# MCU_Signals.net
KiCad netlist of a schematic drawn in Altium Designer
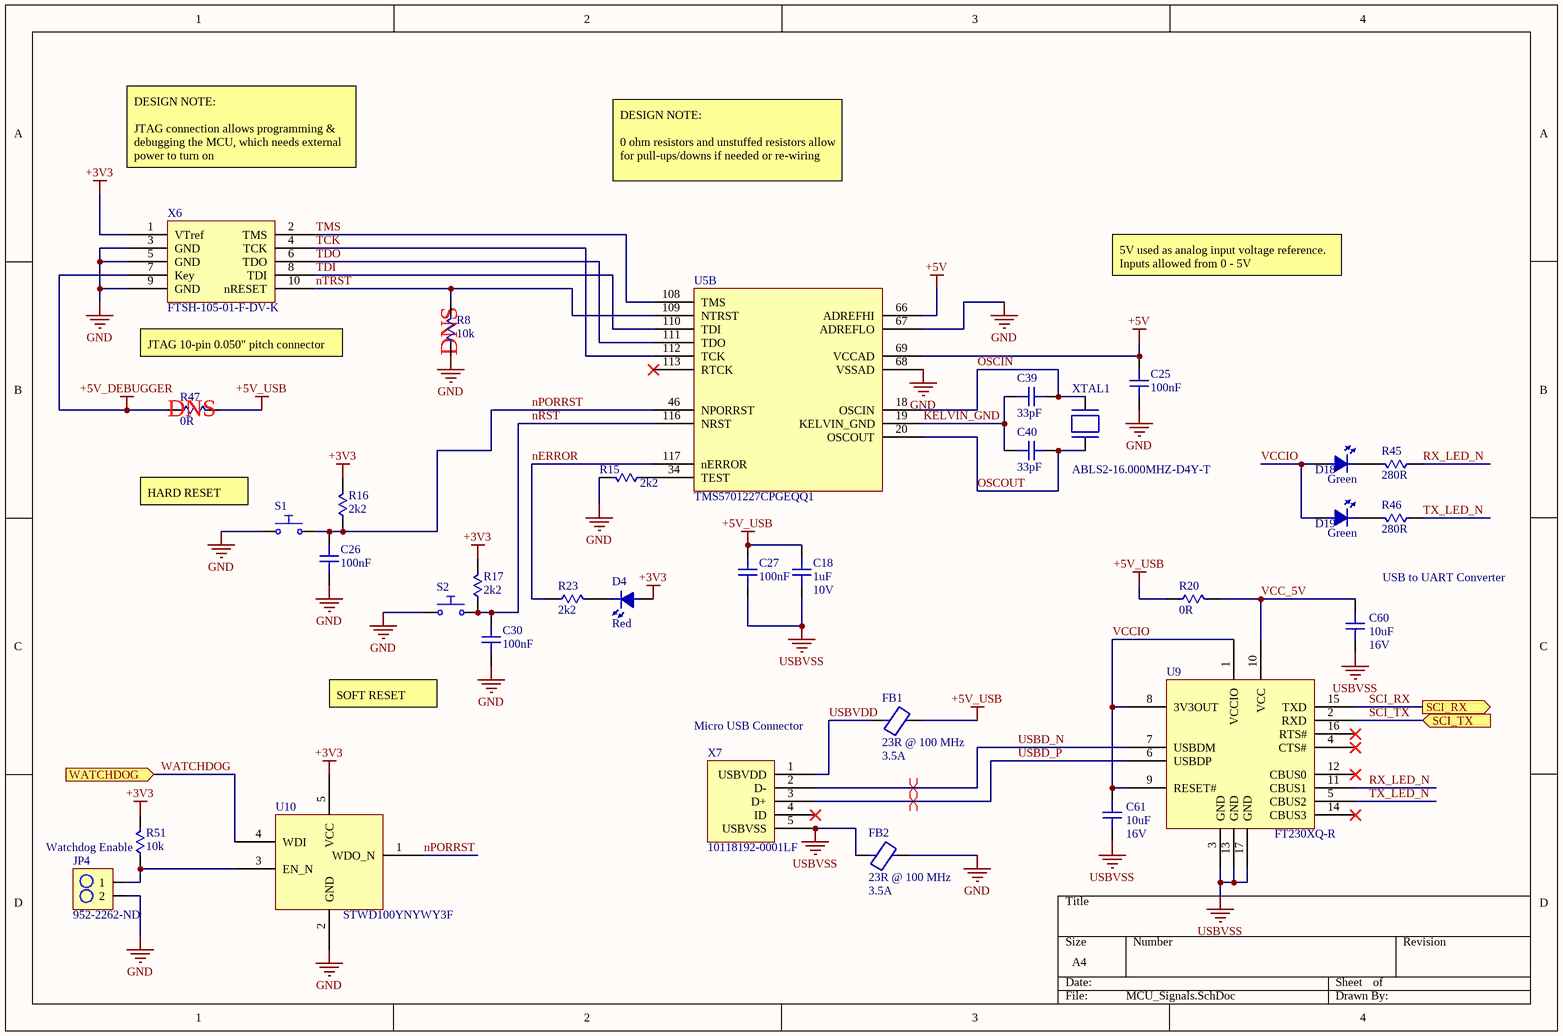
[diagram p0: MCU_Signals.SchDoc]

(export (version "E")
  (design (tool "Eeschema 10.0.6"))
  (components
    (comp (ref "C18")
      (value "1uF")
      (footprint "C0402")
      (description "CAP MLCC 1uF 10V 0402 X5R 20% SMD 0402 85C Paper T/R")
      (fields
        (field (name "MANUFACTURER") "Samsung")
        (field (name "MANUFACTURER PART NUMBER") "CL05A105MP5NNNC")
        (field (name "VOLTAGE RATING") "10V")
      )
      (libsource (lib "PHANTOM_LIBRARY") (part "CL05A105MP5NNNC"))
    )
    (comp (ref "C25")
      (value "100nF")
      (footprint "C0402")
      (description "CAP MLCC 0.1uF 10V X5R 0402 20% SMD 0402 85C Paper T/R")
      (fields
        (field (name "MANUFACTURER") "Samsung")
        (field (name "MANUFACTURER PART NUMBER") "CL05A104MP5NNNC")
      )
      (libsource (lib "PHANTOM_LIBRARY") (part "CL05A104MP5NNNC"))
    )
    (comp (ref "C26")
      (value "100nF")
      (footprint "C0402")
      (description "CAP MLCC 0.1uF 10V X5R 0402 20% SMD 0402 85C Paper T/R")
      (fields
        (field (name "MANUFACTURER") "Samsung")
        (field (name "MANUFACTURER PART NUMBER") "CL05A104MP5NNNC")
      )
      (libsource (lib "PHANTOM_LIBRARY") (part "CL05A104MP5NNNC"))
    )
    (comp (ref "C27")
      (value "100nF")
      (footprint "C0402")
      (description "CAP MLCC 0.1uF 10V X5R 0402 20% SMD 0402 85C Paper T/R")
      (fields
        (field (name "MANUFACTURER") "Samsung")
        (field (name "MANUFACTURER PART NUMBER") "CL05A104MP5NNNC")
      )
      (libsource (lib "PHANTOM_LIBRARY") (part "CL05A104MP5NNNC"))
    )
    (comp (ref "C30")
      (value "100nF")
      (footprint "C0402")
      (description "CAP MLCC 0.1uF 10V X5R 0402 20% SMD 0402 85C Paper T/R")
      (fields
        (field (name "MANUFACTURER") "Samsung")
        (field (name "MANUFACTURER PART NUMBER") "CL05A104MP5NNNC")
      )
      (libsource (lib "PHANTOM_LIBRARY") (part "CL05A104MP5NNNC"))
    )
    (comp (ref "C39")
      (value "33pF")
      (footprint "C0402")
      (description "CAP MLCC 33pF 10V C0G, NP0 0402 (1005 Metric) 0.039\" L x 0.020\" W (1.00mm x 0.50mm)")
      (fields
        (field (name "MANUFACTURER") "Wurth Electronics")
        (field (name "MANUFACTURER PART NUMBER") "885012005010")
      )
      (libsource (lib "PHANTOM_LIBRARY") (part "885012005010"))
    )
    (comp (ref "C40")
      (value "33pF")
      (footprint "C0402")
      (description "CAP MLCC 33pF 10V C0G, NP0 0402 (1005 Metric) 0.039\" L x 0.020\" W (1.00mm x 0.50mm)")
      (fields
        (field (name "MANUFACTURER") "Wurth Electronics")
        (field (name "MANUFACTURER PART NUMBER") "885012005010")
      )
      (libsource (lib "PHANTOM_LIBRARY") (part "885012005010"))
    )
    (comp (ref "C60")
      (value "10uF")
      (footprint "C0805")
      (description "CAP CER 10uF 16V X5R 10% SMD 0805 85C T/R")
      (fields
        (field (name "MANUFACTURER") "Samsung")
        (field (name "MANUFACTURER PART NUMBER") "CL21A106KOQNNNE")
        (field (name "VOLTAGE RATING") "16V")
      )
      (libsource (lib "ESC_SYMBOLS") (part "CL21A106KOQNNNE"))
    )
    (comp (ref "C61")
      (value "10uF")
      (footprint "C0805")
      (description "CAP CER 10uF 16V X5R 10% SMD 0805 85C T/R")
      (fields
        (field (name "MANUFACTURER") "Samsung")
        (field (name "MANUFACTURER PART NUMBER") "CL21A106KOQNNNE")
        (field (name "VOLTAGE RATING") "16V")
      )
      (libsource (lib "ESC_SYMBOLS") (part "CL21A106KOQNNNE"))
    )
    (comp (ref "D4")
      (value "Red")
      (footprint "LED_0603")
      (description "LED RED CLEAR 0603 SMD 625 nm, 2 V, 30 mA, 250 mcd")
      (fields
        (field (name "MANUFACTURER") "Wurth Electronics")
        (field (name "MANUFACTURER PART NUMBER") "150060RS75000")
      )
      (libsource (lib "PHANTOM_LIBRARY") (part "150060RS75000"))
    )
    (comp (ref "D18")
      (value "Green")
      (footprint "LED_0603")
      (description "LED GREEN CLEAR 0603 SMD  LED, 0603, B GREEN,  40MCD, 570NM")
      (fields
        (field (name "MANUFACTURER") "Wurth Electronics")
        (field (name "MANUFACTURER PART NUMBER") "150060VS75000")
      )
      (libsource (lib "PHANTOM_LIBRARY") (part "150060VS75000"))
    )
    (comp (ref "D19")
      (value "Green")
      (footprint "LED_0603")
      (description "LED GREEN CLEAR 0603 SMD  LED, 0603, B GREEN,  40MCD, 570NM")
      (fields
        (field (name "MANUFACTURER") "Wurth Electronics")
        (field (name "MANUFACTURER PART NUMBER") "150060VS75000")
      )
      (libsource (lib "PHANTOM_LIBRARY") (part "150060VS75000"))
    )
    (comp (ref "FB1")
      (value "23R @ 100 MHz")
      (footprint "FB_1806")
      (description "FERRITE BEAD Ind Chip Bead Multi-Layer 23Ohm 30% 100MHz Ferrite 3.5A 1806 T/R")
      (fields
        (field (name "MANUFACTURER") "Taiyo Yuden")
        (field (name "MANUFACTURER PART NUMBER") "FBMJ4516HL230NTV")
        (field (name "MAX CURRENT RATING") "3.5A")
      )
      (libsource (lib "PHANTOM_LIBRARY") (part "FBMJ4516HL230NTV"))
    )
    (comp (ref "FB2")
      (value "23R @ 100 MHz")
      (footprint "FB_1806")
      (description "FERRITE BEAD Ind Chip Bead Multi-Layer 23Ohm 30% 100MHz Ferrite 3.5A 1806 T/R")
      (fields
        (field (name "MANUFACTURER") "Taiyo Yuden")
        (field (name "MANUFACTURER PART NUMBER") "FBMJ4516HL230NTV")
        (field (name "MAX CURRENT RATING") "3.5A")
      )
      (libsource (lib "PHANTOM_LIBRARY") (part "FBMJ4516HL230NTV"))
    )
    (comp (ref "JP4")
      (value "952-2262-ND")
      (footprint "2PIN_HEADER")
      (description "CONN_HeaderPins2pos Headers & Wire Housings 02 SIL VERTICAL PIN HEADER TIN")
      (fields (field (name "MANUFACTURER") "Harwin") (field (name "MANUFACTURER PART NUMBER") "M20-9990246"))
      (libsource (lib "PHANTOM_LIBRARY") (part "M20-9990246"))
    )
    (comp (ref "R8")
      (value "10k")
      (footprint "R0402")
      (description "RES SMD 10K OHM 5% 1/16W 0402")
      (fields
        (field (name "MANUFACTURER") "Yageo")
        (field (name "MANUFACTURER PART NUMBER") "RC0402JR-0710KL")
      )
      (libsource (lib "PHANTOM_LIBRARY") (part "RC0402JR-0710KL"))
    )
    (comp (ref "R15")
      (value "2k2")
      (footprint "R0402")
      (description "RES SMD 2.2K OHM 5% 1/16W 0402")
      (fields
        (field (name "MANUFACTURER") "Yageo")
        (field (name "MANUFACTURER PART NUMBER") "RC0402JR-072K2L")
      )
      (libsource (lib "PHANTOM_LIBRARY") (part "RC0402JR-072K2L"))
    )
    (comp (ref "R16")
      (value "2k2")
      (footprint "R0402")
      (description "RES SMD 2.2K OHM 5% 1/16W 0402")
      (fields
        (field (name "MANUFACTURER") "Yageo")
        (field (name "MANUFACTURER PART NUMBER") "RC0402JR-072K2L")
      )
      (libsource (lib "PHANTOM_LIBRARY") (part "RC0402JR-072K2L"))
    )
    (comp (ref "R17")
      (value "2k2")
      (footprint "R0402")
      (description "RES SMD 2.2K OHM 5% 1/16W 0402")
      (fields
        (field (name "MANUFACTURER") "Yageo")
        (field (name "MANUFACTURER PART NUMBER") "RC0402JR-072K2L")
      )
      (libsource (lib "PHANTOM_LIBRARY") (part "RC0402JR-072K2L"))
    )
    (comp (ref "R20")
      (value "0R")
      (footprint "R0402")
      (description "RES SMD 0 OHM 1/16W 0402")
      (fields
        (field (name "MANUFACTURER") "Yageo")
        (field (name "MANUFACTURER PART NUMBER") "RC0402JR-070RL")
      )
      (libsource (lib "BT_SYMBOLS") (part "RC0402JR-070RL"))
    )
    (comp (ref "R23")
      (value "2k2")
      (footprint "R0402")
      (description "RES SMD 2.2K OHM 5% 1/16W 0402")
      (fields
        (field (name "MANUFACTURER") "Yageo")
        (field (name "MANUFACTURER PART NUMBER") "RC0402JR-072K2L")
      )
      (libsource (lib "PHANTOM_LIBRARY") (part "RC0402JR-072K2L"))
    )
    (comp (ref "R45")
      (value "280R")
      (footprint "R0402")
      (description "RES SMD 280 OHM 1% 1/16W 0402")
      (fields
        (field (name "MANUFACTURER") "Yageo")
        (field (name "MANUFACTURER PART NUMBER") "RC0402FR-07280RL")
      )
      (libsource (lib "PHANTOM_LIBRARY") (part "RC0402FR-07280RL"))
    )
    (comp (ref "R46")
      (value "280R")
      (footprint "R0402")
      (description "RES SMD 280 OHM 1% 1/16W 0402")
      (fields
        (field (name "MANUFACTURER") "Yageo")
        (field (name "MANUFACTURER PART NUMBER") "RC0402FR-07280RL")
      )
      (libsource (lib "PHANTOM_LIBRARY") (part "RC0402FR-07280RL"))
    )
    (comp (ref "R47")
      (value "0R")
      (footprint "R0402")
      (description "RES SMD 0 OHM 1/16W 0402")
      (fields
        (field (name "MANUFACTURER") "Yageo")
        (field (name "MANUFACTURER PART NUMBER") "RC0402JR-070RL")
      )
      (libsource (lib "BT_SYMBOLS") (part "RC0402JR-070RL"))
    )
    (comp (ref "R51")
      (value "10k")
      (footprint "R0402")
      (description "RES SMD 10K OHM 5% 1/16W 0402")
      (fields
        (field (name "MANUFACTURER") "Yageo")
        (field (name "MANUFACTURER PART NUMBER") "RC0402JR-0710KL")
      )
      (libsource (lib "PHANTOM_LIBRARY") (part "RC0402JR-0710KL"))
    )
    (comp (ref "S1")
      (value "PTS645SM43SMTR92LFS")
      (footprint "PUSH_BUTTON")
      (description "SWITCH TACTILE SPST-NO 0.05A 12V")
      (fields (field (name "MANUFACTURER") "ITT C&K"))
      (libsource (lib "PHANTOM_LIBRARY") (part "PTS645SM43SMTR92LFS"))
    )
    (comp (ref "S2")
      (value "PTS645SM43SMTR92LFS")
      (footprint "PUSH_BUTTON")
      (description "SWITCH TACTILE SPST-NO 0.05A 12V")
      (fields (field (name "MANUFACTURER") "ITT C&K"))
      (libsource (lib "PHANTOM_LIBRARY") (part "PTS645SM43SMTR92LFS"))
    )
    (comp (ref "U5")
      (value "TMS5701227CPGEQQ1")
      (footprint "LQFP-144")
      (description "IC MCU 16-Bit/32-Bit Hercules TMS570 ARM Cortex R4F RISC 1280KB Flash 1.2V/3.3V 144-Pin LQFP")
      (fields (field (name "MANUFACTURER") "Texas Instruments"))
      (libsource (lib "PHANTOM_LIBRARY") (part "TMS5701227CPGEQQ1"))
    )
    (comp (ref "U9")
      (value "FT230XQ-R")
      (footprint "QFN16-EP")
      (description "IC USB SERIAL BASIC UART 16QFN")
      (fields (field (name "MANUFACTURER") "FTDI"))
      (libsource (lib "PHANTOM_LIBRARY") (part "FT230XQ-R"))
    )
    (comp (ref "U10")
      (value "STWD100YNYWY3F")
      (footprint "SOT23-5-WATCHDOG")
      (description "IC WATCHDOG TIME CIRCUIT SOT23-5")
      (fields (field (name "MANUFACTURER") "STMicroelectronics"))
      (libsource (lib "PHANTOM_LIBRARY") (part "STWD100YNYWY3F"))
    )
    (comp (ref "X6")
      (value "FTSH-105-01-F-DV-K")
      (footprint "JTAG_50mil_10pin")
      (description "CONN_JTAG_10pin .050 Connector Dual Header 10 Position Surface Mount")
      (fields (field (name "MANUFACTURER") "Samtec"))
      (libsource (lib "PHANTOM_LIBRARY") (part "FTSH-105-01-F-DV-K"))
    )
    (comp (ref "X7")
      (value "10118192-0001LF")
      (footprint "USB_MICRO")
      (description "CONN_USB - micro B USB 2.0 Receptacle Connector 5 Position Surface Mount, Right Angle, Horizontal")
      (fields (field (name "MANUFACTURER") "Amphenol FCI"))
      (libsource (lib "PHANTOM_LIBRARY") (part "10118192-0001LF"))
    )
    (comp (ref "XTAL1")
      (value "ABLS2-16.000MHZ-D4Y-T")
      (footprint "XTAL")
      (description "XTAL 16MHz ±30ppm Crystal 18pF 40 Ohm -40°C ~ 85°C  Surface Mount HC49/US")
      (fields (field (name "MANUFACTURER") "Abracon") (field (name "TOLERANCE") "30ppm"))
      (libsource (lib "PHANTOM_LIBRARY") (part "ABLS2-16.000MHZ-D4Y-T"))
    )
  )
  (nets
    (net (code "1") (name "+3V3") (class "Default")
      (node (ref "D4") (pin "1") (pinfunction "1_1") (pintype "passive"))
      (node (ref "R16") (pin "2") (pinfunction "2_2") (pintype "passive"))
      (node (ref "R17") (pin "2") (pinfunction "2_2") (pintype "passive"))
      (node (ref "R51") (pin "2") (pinfunction "2_2") (pintype "passive"))
      (node (ref "U10") (pin "5") (pinfunction "VCC_5") (pintype "passive"))
      (node (ref "X6") (pin "1") (pinfunction "VTref_1") (pintype "passive"))
    )
    (net (code "2") (name "+5V") (class "Default")
      (node (ref "C25") (pin "2") (pinfunction "2_2") (pintype "passive"))
      (node (ref "U5") (pin "66") (pinfunction "ADREFHI_66") (pintype "passive"))
      (node (ref "U5") (pin "69") (pinfunction "VCCAD_69") (pintype "passive"))
    )
    (net (code "3") (name "+5V_DEBUGGER") (class "Default")
      (node (ref "R47") (pin "1") (pinfunction "1_1") (pintype "passive"))
      (node (ref "X6") (pin "7") (pinfunction "Key_7") (pintype "passive"))
    )
    (net (code "4") (name "+5V_USB") (class "Default")
      (node (ref "C18") (pin "2") (pinfunction "2_2") (pintype "passive"))
      (node (ref "C27") (pin "1") (pinfunction "1_1") (pintype "passive"))
      (node (ref "FB1") (pin "2") (pinfunction "2_2") (pintype "passive"))
      (node (ref "R20") (pin "1") (pinfunction "1_1") (pintype "passive"))
      (node (ref "R47") (pin "2") (pinfunction "2_2") (pintype "passive"))
    )
    (net (code "5") (name "/KELVIN_GND") (class "Default")
      (node (ref "C39") (pin "2") (pinfunction "2_2") (pintype "passive"))
      (node (ref "C40") (pin "2") (pinfunction "2_2") (pintype "passive"))
      (node (ref "U5") (pin "19") (pinfunction "KELVIN_GND_19") (pintype "passive"))
    )
    (net (code "6") (name "/OSCIN") (class "Default")
      (node (ref "C39") (pin "1") (pinfunction "1_1") (pintype "passive"))
      (node (ref "U5") (pin "18") (pinfunction "OSCIN_18") (pintype "passive"))
      (node (ref "XTAL1") (pin "1") (pintype "passive"))
    )
    (net (code "7") (name "/OSCOUT") (class "Default")
      (node (ref "C40") (pin "1") (pinfunction "1_1") (pintype "passive"))
      (node (ref "U5") (pin "20") (pinfunction "OSCOUT_20") (pintype "passive"))
      (node (ref "XTAL1") (pin "2") (pintype "passive"))
    )
    (net (code "8") (name "/RX_LED_N") (class "Default")
      (node (ref "R45") (pin "1") (pinfunction "1_1") (pintype "passive"))
      (node (ref "U9") (pin "11") (pinfunction "CBUS1_11") (pintype "passive"))
    )
    (net (code "9") (name "/SCI_RX") (class "Default")
      (node (ref "U9") (pin "15") (pinfunction "TXD_15") (pintype "passive"))
    )
    (net (code "10") (name "/SCI_TX") (class "Default")
      (node (ref "U9") (pin "2") (pinfunction "RXD_2") (pintype "passive"))
    )
    (net (code "11") (name "/TCK") (class "Default")
      (node (ref "U5") (pin "112") (pinfunction "TCK_112") (pintype "passive"))
      (node (ref "X6") (pin "4") (pinfunction "TCK_4") (pintype "passive"))
    )
    (net (code "12") (name "/TDI") (class "Default")
      (node (ref "U5") (pin "110") (pinfunction "TDI_110") (pintype "passive"))
      (node (ref "X6") (pin "8") (pinfunction "TDI_8") (pintype "passive"))
    )
    (net (code "13") (name "/TDO") (class "Default")
      (node (ref "U5") (pin "111") (pinfunction "TDO_111") (pintype "passive"))
      (node (ref "X6") (pin "6") (pinfunction "TDO_6") (pintype "passive"))
    )
    (net (code "14") (name "/TMS") (class "Default")
      (node (ref "U5") (pin "108") (pinfunction "TMS_108") (pintype "passive"))
      (node (ref "X6") (pin "2") (pinfunction "TMS_2") (pintype "passive"))
    )
    (net (code "15") (name "/TX_LED_N") (class "Default")
      (node (ref "R46") (pin "1") (pinfunction "1_1") (pintype "passive"))
      (node (ref "U9") (pin "5") (pinfunction "CBUS2_5") (pintype "passive"))
    )
    (net (code "16") (name "/USBD_N") (class "Default")
      (node (ref "U9") (pin "7") (pinfunction "USBDM_7") (pintype "passive"))
      (node (ref "X7") (pin "2") (pinfunction "D-_2") (pintype "passive"))
    )
    (net (code "17") (name "/USBD_P") (class "Default")
      (node (ref "U9") (pin "6") (pinfunction "USBDP_6") (pintype "passive"))
      (node (ref "X7") (pin "3") (pinfunction "D+_3") (pintype "passive"))
    )
    (net (code "18") (name "/USBVDD") (class "Default")
      (node (ref "FB1") (pin "1") (pinfunction "1_1") (pintype "passive"))
      (node (ref "X7") (pin "1") (pinfunction "USBVDD_1") (pintype "passive"))
    )
    (net (code "19") (name "/VCCIO") (class "Default")
      (node (ref "C61") (pin "2") (pinfunction "2_2") (pintype "passive"))
      (node (ref "D18") (pin "1") (pinfunction "1_1") (pintype "passive"))
      (node (ref "D19") (pin "1") (pinfunction "1_1") (pintype "passive"))
      (node (ref "U9") (pin "1") (pinfunction "VCCIO_1") (pintype "passive"))
      (node (ref "U9") (pin "8") (pinfunction "3V3OUT_8") (pintype "passive"))
      (node (ref "U9") (pin "9") (pinfunction "RESET#_9") (pintype "passive"))
    )
    (net (code "20") (name "/VCC_5V") (class "Default")
      (node (ref "C60") (pin "2") (pinfunction "2_2") (pintype "passive"))
      (node (ref "R20") (pin "2") (pinfunction "2_2") (pintype "passive"))
      (node (ref "U9") (pin "10") (pinfunction "VCC_10") (pintype "passive"))
    )
    (net (code "21") (name "/WATCHDOG") (class "Default")
      (node (ref "U10") (pin "4") (pinfunction "WDI_4") (pintype "passive"))
    )
    (net (code "22") (name "/nERROR") (class "Default")
      (node (ref "R23") (pin "1") (pinfunction "1_1") (pintype "passive"))
      (node (ref "U5") (pin "117") (pinfunction "nERROR_117") (pintype "passive"))
    )
    (net (code "23") (name "/nPORRST") (class "Default")
      (node (ref "C26") (pin "2") (pinfunction "2_2") (pintype "passive"))
      (node (ref "R16") (pin "1") (pinfunction "1_1") (pintype "passive"))
      (node (ref "S1") (pin "2") (pinfunction "2_2") (pintype "passive"))
      (node (ref "U10") (pin "1") (pinfunction "WDO_N_1") (pintype "passive"))
      (node (ref "U5") (pin "46") (pinfunction "NPORRST_46") (pintype "passive"))
    )
    (net (code "24") (name "/nRST") (class "Default")
      (node (ref "C30") (pin "2") (pinfunction "2_2") (pintype "passive"))
      (node (ref "R17") (pin "1") (pinfunction "1_1") (pintype "passive"))
      (node (ref "S2") (pin "2") (pinfunction "2_2") (pintype "passive"))
      (node (ref "U5") (pin "116") (pinfunction "NRST_116") (pintype "passive"))
    )
    (net (code "25") (name "/nTRST") (class "Default")
      (node (ref "R8") (pin "2") (pinfunction "2_2") (pintype "passive"))
      (node (ref "U5") (pin "109") (pinfunction "NTRST_109") (pintype "passive"))
      (node (ref "X6") (pin "10") (pinfunction "nRESET_10") (pintype "passive"))
    )
    (net (code "26") (name "GND") (class "Default")
      (node (ref "C25") (pin "1") (pinfunction "1_1") (pintype "passive"))
      (node (ref "C26") (pin "1") (pinfunction "1_1") (pintype "passive"))
      (node (ref "C30") (pin "1") (pinfunction "1_1") (pintype "passive"))
      (node (ref "FB2") (pin "2") (pinfunction "2_2") (pintype "passive"))
      (node (ref "JP4") (pin "2") (pinfunction "2_2") (pintype "passive"))
      (node (ref "R15") (pin "2") (pinfunction "2_2") (pintype "passive"))
      (node (ref "R8") (pin "1") (pinfunction "1_1") (pintype "passive"))
      (node (ref "S1") (pin "1") (pinfunction "1_1") (pintype "passive"))
      (node (ref "S2") (pin "1") (pinfunction "1_1") (pintype "passive"))
      (node (ref "U10") (pin "2") (pinfunction "GND_2") (pintype "passive"))
      (node (ref "U5") (pin "67") (pinfunction "ADREFLO_67") (pintype "passive"))
      (node (ref "U5") (pin "68") (pinfunction "VSSAD_68") (pintype "passive"))
      (node (ref "X6") (pin "3") (pinfunction "GND_3") (pintype "passive"))
      (node (ref "X6") (pin "5") (pinfunction "GND_5") (pintype "passive"))
      (node (ref "X6") (pin "9") (pinfunction "GND_9") (pintype "passive"))
    )
    (net (code "27") (name "Net-(D4-Pad2)") (class "Default")
      (node (ref "D4") (pin "2") (pinfunction "2_2") (pintype "passive"))
      (node (ref "R23") (pin "2") (pinfunction "2_2") (pintype "passive"))
    )
    (net (code "28") (name "Net-(D18-Pad2)") (class "Default")
      (node (ref "D18") (pin "2") (pinfunction "2_2") (pintype "passive"))
      (node (ref "R45") (pin "2") (pinfunction "2_2") (pintype "passive"))
    )
    (net (code "29") (name "Net-(D19-Pad2)") (class "Default")
      (node (ref "D19") (pin "2") (pinfunction "2_2") (pintype "passive"))
      (node (ref "R46") (pin "2") (pinfunction "2_2") (pintype "passive"))
    )
    (net (code "30") (name "Net-(U5B-TEST)") (class "Default")
      (node (ref "R15") (pin "1") (pinfunction "1_1") (pintype "passive"))
      (node (ref "U5") (pin "34") (pinfunction "TEST_34") (pintype "passive"))
    )
    (net (code "31") (name "Net-(U10-EN_N)") (class "Default")
      (node (ref "JP4") (pin "1") (pinfunction "1_1") (pintype "passive"))
      (node (ref "R51") (pin "1") (pinfunction "1_1") (pintype "passive"))
      (node (ref "U10") (pin "3") (pinfunction "EN_N_3") (pintype "passive"))
    )
    (net (code "32") (name "USBVSS") (class "Default")
      (node (ref "C18") (pin "1") (pinfunction "1_1") (pintype "passive"))
      (node (ref "C27") (pin "2") (pinfunction "2_2") (pintype "passive"))
      (node (ref "C60") (pin "1") (pinfunction "1_1") (pintype "passive"))
      (node (ref "C61") (pin "1") (pinfunction "1_1") (pintype "passive"))
      (node (ref "FB2") (pin "1") (pinfunction "1_1") (pintype "passive"))
      (node (ref "U9") (pin "13") (pinfunction "GND_13") (pintype "passive"))
      (node (ref "U9") (pin "17") (pinfunction "GND_17") (pintype "passive"))
      (node (ref "U9") (pin "3") (pinfunction "GND_3") (pintype "passive"))
      (node (ref "X7") (pin "5") (pinfunction "USBVSS_5") (pintype "passive"))
    )
    (net (code "33") (name "unconnected-(U5B-RTCK-Pad113)") (class "Default")
      (node (ref "U5") (pin "113") (pinfunction "RTCK_113") (pintype "passive+no_connect"))
    )
    (net (code "34") (name "unconnected-(U9-CBUS0-Pad12)") (class "Default")
      (node (ref "U9") (pin "12") (pinfunction "CBUS0_12") (pintype "passive+no_connect"))
    )
    (net (code "35") (name "unconnected-(U9-CBUS3-Pad14)") (class "Default")
      (node (ref "U9") (pin "14") (pinfunction "CBUS3_14") (pintype "passive+no_connect"))
    )
    (net (code "36") (name "unconnected-(U9-CTS#-Pad4)") (class "Default")
      (node (ref "U9") (pin "4") (pinfunction "CTS#_4") (pintype "passive+no_connect"))
    )
    (net (code "37") (name "unconnected-(U9-RTS#-Pad16)") (class "Default")
      (node (ref "U9") (pin "16") (pinfunction "RTS#_16") (pintype "passive+no_connect"))
    )
    (net (code "38") (name "unconnected-(X7-ID-Pad4)") (class "Default")
      (node (ref "X7") (pin "4") (pinfunction "ID_4") (pintype "passive+no_connect"))
    )
  )
)
